# 328-programmer.net
KiCad netlist of a schematic drawn in EAGLE
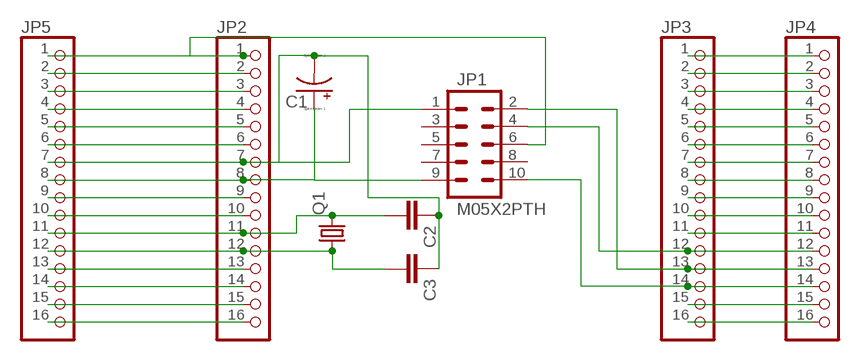
[diagram p0: schematic, sheet 1]

(export (version "E")
  (design (tool "Eeschema 10.0.6"))
  (components
    (comp (ref "C1")
      (value "CPOL-USE2.5-7")
      (footprint "eagle-import:E2,5-7")
      (libsource (lib "eagle-import") (part "CPOL-USE2.5-7"))
    )
    (comp (ref "C2")
      (value "CAPPTH2")
      (footprint "eagle-import:CAP-PTH-SMALL2")
      (libsource (lib "eagle-import") (part "CAPPTH2"))
    )
    (comp (ref "C3")
      (value "CAPPTH2")
      (footprint "eagle-import:CAP-PTH-SMALL2")
      (libsource (lib "eagle-import") (part "CAPPTH2"))
    )
    (comp (ref "JP1")
      (value "M05X2PTH")
      (footprint "eagle-import:AVR_ICSP")
      (libsource (lib "eagle-import") (part "M05X2PTH"))
    )
    (comp (ref "JP2")
      (value "PINHD-1X16")
      (footprint "eagle-import:1X16")
      (libsource (lib "eagle-import") (part "PINHD-1X16"))
    )
    (comp (ref "JP3")
      (value "PINHD-1X16")
      (footprint "eagle-import:1X16")
      (libsource (lib "eagle-import") (part "PINHD-1X16"))
    )
    (comp (ref "JP4")
      (value "PINHD-1X16")
      (footprint "eagle-import:1X16")
      (libsource (lib "eagle-import") (part "PINHD-1X16"))
    )
    (comp (ref "JP5")
      (value "PINHD-1X16")
      (footprint "eagle-import:1X16")
      (libsource (lib "eagle-import") (part "PINHD-1X16"))
    )
    (comp (ref "Q1")
      (value "CRYSTALHC49S")
      (footprint "eagle-import:HC49_S")
      (libsource (lib "eagle-import") (part "CRYSTALHC49S"))
    )
  )
  (nets
    (net (code "1") (name "Net-(C1-Pad+)") (class "Default")
      (node (ref "C1") (pin "+") (pinfunction "+_+") (pintype "passive"))
      (node (ref "JP1") (pin "9") (pinfunction "9_9") (pintype "passive"))
      (node (ref "JP2") (pin "8") (pinfunction "8_8") (pintype "passive"))
      (node (ref "JP5") (pin "8") (pinfunction "8_8") (pintype "passive"))
    )
    (net (code "2") (name "Net-(C1-Pad-)") (class "Default")
      (node (ref "C1") (pin "-") (pinfunction "-_-") (pintype "passive"))
      (node (ref "C2") (pin "1") (pinfunction "1_1") (pintype "passive"))
      (node (ref "C3") (pin "1") (pinfunction "1_1") (pintype "passive"))
      (node (ref "JP1") (pin "1") (pinfunction "1_1") (pintype "passive"))
      (node (ref "JP2") (pin "7") (pinfunction "7_7") (pintype "passive"))
      (node (ref "JP5") (pin "7") (pinfunction "7_7") (pintype "passive"))
    )
    (net (code "3") (name "Net-(C2-Pad2)") (class "Default")
      (node (ref "C2") (pin "2") (pinfunction "2_2") (pintype "passive"))
      (node (ref "JP2") (pin "11") (pinfunction "11_11") (pintype "passive"))
      (node (ref "JP5") (pin "11") (pinfunction "11_11") (pintype "passive"))
      (node (ref "Q1") (pin "2") (pinfunction "2_2") (pintype "passive"))
    )
    (net (code "4") (name "Net-(C3-Pad2)") (class "Default")
      (node (ref "C3") (pin "2") (pinfunction "2_2") (pintype "passive"))
      (node (ref "JP2") (pin "12") (pinfunction "12_12") (pintype "passive"))
      (node (ref "JP5") (pin "12") (pinfunction "12_12") (pintype "passive"))
      (node (ref "Q1") (pin "1") (pinfunction "1_1") (pintype "passive"))
    )
    (net (code "5") (name "Net-(JP1-Pad2)") (class "Default")
      (node (ref "JP1") (pin "2") (pinfunction "2_2") (pintype "passive"))
      (node (ref "JP3") (pin "13") (pinfunction "13_13") (pintype "passive"))
      (node (ref "JP4") (pin "13") (pinfunction "13_13") (pintype "passive"))
    )
    (net (code "6") (name "Net-(JP1-Pad4)") (class "Default")
      (node (ref "JP1") (pin "4") (pinfunction "4_4") (pintype "passive"))
      (node (ref "JP3") (pin "12") (pinfunction "12_12") (pintype "passive"))
      (node (ref "JP4") (pin "12") (pinfunction "12_12") (pintype "passive"))
    )
    (net (code "7") (name "Net-(JP1-Pad6)") (class "Default")
      (node (ref "JP1") (pin "6") (pinfunction "6_6") (pintype "passive"))
      (node (ref "JP2") (pin "1") (pinfunction "1_1") (pintype "passive"))
      (node (ref "JP5") (pin "1") (pinfunction "1_1") (pintype "passive"))
    )
    (net (code "8") (name "Net-(JP1-Pad10)") (class "Default")
      (node (ref "JP1") (pin "10") (pinfunction "10_10") (pintype "passive"))
      (node (ref "JP3") (pin "14") (pinfunction "14_14") (pintype "passive"))
      (node (ref "JP4") (pin "14") (pinfunction "14_14") (pintype "passive"))
    )
    (net (code "9") (name "Net-(JP2-Pad2)") (class "Default")
      (node (ref "JP2") (pin "2") (pinfunction "2_2") (pintype "passive"))
      (node (ref "JP5") (pin "2") (pinfunction "2_2") (pintype "passive"))
    )
    (net (code "10") (name "Net-(JP2-Pad3)") (class "Default")
      (node (ref "JP2") (pin "3") (pinfunction "3_3") (pintype "passive"))
      (node (ref "JP5") (pin "3") (pinfunction "3_3") (pintype "passive"))
    )
    (net (code "11") (name "Net-(JP2-Pad4)") (class "Default")
      (node (ref "JP2") (pin "4") (pinfunction "4_4") (pintype "passive"))
      (node (ref "JP5") (pin "4") (pinfunction "4_4") (pintype "passive"))
    )
    (net (code "12") (name "Net-(JP2-Pad5)") (class "Default")
      (node (ref "JP2") (pin "5") (pinfunction "5_5") (pintype "passive"))
      (node (ref "JP5") (pin "5") (pinfunction "5_5") (pintype "passive"))
    )
    (net (code "13") (name "Net-(JP2-Pad6)") (class "Default")
      (node (ref "JP2") (pin "6") (pinfunction "6_6") (pintype "passive"))
      (node (ref "JP5") (pin "6") (pinfunction "6_6") (pintype "passive"))
    )
    (net (code "14") (name "Net-(JP2-Pad9)") (class "Default")
      (node (ref "JP2") (pin "9") (pinfunction "9_9") (pintype "passive"))
      (node (ref "JP5") (pin "9") (pinfunction "9_9") (pintype "passive"))
    )
    (net (code "15") (name "Net-(JP2-Pad10)") (class "Default")
      (node (ref "JP2") (pin "10") (pinfunction "10_10") (pintype "passive"))
      (node (ref "JP5") (pin "10") (pinfunction "10_10") (pintype "passive"))
    )
    (net (code "16") (name "Net-(JP2-Pad13)") (class "Default")
      (node (ref "JP2") (pin "13") (pinfunction "13_13") (pintype "passive"))
      (node (ref "JP5") (pin "13") (pinfunction "13_13") (pintype "passive"))
    )
    (net (code "17") (name "Net-(JP2-Pad14)") (class "Default")
      (node (ref "JP2") (pin "14") (pinfunction "14_14") (pintype "passive"))
      (node (ref "JP5") (pin "14") (pinfunction "14_14") (pintype "passive"))
    )
    (net (code "18") (name "Net-(JP2-Pad15)") (class "Default")
      (node (ref "JP2") (pin "15") (pinfunction "15_15") (pintype "passive"))
      (node (ref "JP5") (pin "15") (pinfunction "15_15") (pintype "passive"))
    )
    (net (code "19") (name "Net-(JP2-Pad16)") (class "Default")
      (node (ref "JP2") (pin "16") (pinfunction "16_16") (pintype "passive"))
      (node (ref "JP5") (pin "16") (pinfunction "16_16") (pintype "passive"))
    )
    (net (code "20") (name "Net-(JP3-Pad1)") (class "Default")
      (node (ref "JP3") (pin "1") (pinfunction "1_1") (pintype "passive"))
      (node (ref "JP4") (pin "1") (pinfunction "1_1") (pintype "passive"))
    )
    (net (code "21") (name "Net-(JP3-Pad2)") (class "Default")
      (node (ref "JP3") (pin "2") (pinfunction "2_2") (pintype "passive"))
      (node (ref "JP4") (pin "2") (pinfunction "2_2") (pintype "passive"))
    )
    (net (code "22") (name "Net-(JP3-Pad3)") (class "Default")
      (node (ref "JP3") (pin "3") (pinfunction "3_3") (pintype "passive"))
      (node (ref "JP4") (pin "3") (pinfunction "3_3") (pintype "passive"))
    )
    (net (code "23") (name "Net-(JP3-Pad4)") (class "Default")
      (node (ref "JP3") (pin "4") (pinfunction "4_4") (pintype "passive"))
      (node (ref "JP4") (pin "4") (pinfunction "4_4") (pintype "passive"))
    )
    (net (code "24") (name "Net-(JP3-Pad5)") (class "Default")
      (node (ref "JP3") (pin "5") (pinfunction "5_5") (pintype "passive"))
      (node (ref "JP4") (pin "5") (pinfunction "5_5") (pintype "passive"))
    )
    (net (code "25") (name "Net-(JP3-Pad6)") (class "Default")
      (node (ref "JP3") (pin "6") (pinfunction "6_6") (pintype "passive"))
      (node (ref "JP4") (pin "6") (pinfunction "6_6") (pintype "passive"))
    )
    (net (code "26") (name "Net-(JP3-Pad7)") (class "Default")
      (node (ref "JP3") (pin "7") (pinfunction "7_7") (pintype "passive"))
      (node (ref "JP4") (pin "7") (pinfunction "7_7") (pintype "passive"))
    )
    (net (code "27") (name "Net-(JP3-Pad8)") (class "Default")
      (node (ref "JP3") (pin "8") (pinfunction "8_8") (pintype "passive"))
      (node (ref "JP4") (pin "8") (pinfunction "8_8") (pintype "passive"))
    )
    (net (code "28") (name "Net-(JP3-Pad9)") (class "Default")
      (node (ref "JP3") (pin "9") (pinfunction "9_9") (pintype "passive"))
      (node (ref "JP4") (pin "9") (pinfunction "9_9") (pintype "passive"))
    )
    (net (code "29") (name "Net-(JP3-Pad10)") (class "Default")
      (node (ref "JP3") (pin "10") (pinfunction "10_10") (pintype "passive"))
      (node (ref "JP4") (pin "10") (pinfunction "10_10") (pintype "passive"))
    )
    (net (code "30") (name "Net-(JP3-Pad11)") (class "Default")
      (node (ref "JP3") (pin "11") (pinfunction "11_11") (pintype "passive"))
      (node (ref "JP4") (pin "11") (pinfunction "11_11") (pintype "passive"))
    )
    (net (code "31") (name "Net-(JP3-Pad15)") (class "Default")
      (node (ref "JP3") (pin "15") (pinfunction "15_15") (pintype "passive"))
      (node (ref "JP4") (pin "15") (pinfunction "15_15") (pintype "passive"))
    )
    (net (code "32") (name "Net-(JP3-Pad16)") (class "Default")
      (node (ref "JP3") (pin "16") (pinfunction "16_16") (pintype "passive"))
      (node (ref "JP4") (pin "16") (pinfunction "16_16") (pintype "passive"))
    )
    (net (code "33") (name "unconnected-(JP1-Pad3)") (class "Default")
      (node (ref "JP1") (pin "3") (pinfunction "3_3") (pintype "passive"))
    )
    (net (code "34") (name "unconnected-(JP1-Pad5)") (class "Default")
      (node (ref "JP1") (pin "5") (pinfunction "5_5") (pintype "passive"))
    )
    (net (code "35") (name "unconnected-(JP1-Pad7)") (class "Default")
      (node (ref "JP1") (pin "7") (pinfunction "7_7") (pintype "passive"))
    )
    (net (code "36") (name "unconnected-(JP1-Pad8)") (class "Default")
      (node (ref "JP1") (pin "8") (pinfunction "8_8") (pintype "passive"))
    )
  )
)
